# Control.net
KiCad netlist of a schematic drawn in Altium Designer
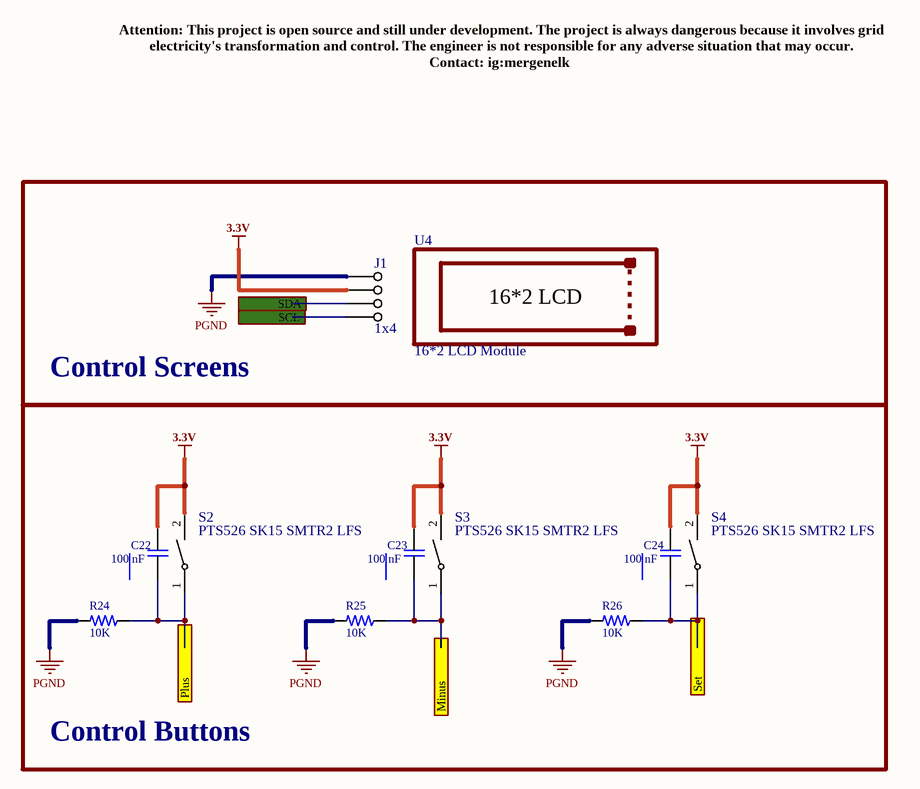
[diagram p0: Control.SchDoc]

(export (version "E")
  (design (tool "Eeschema 10.0.6"))
  (components
    (comp (ref "C22")
      (value "100 nF")
      (footprint "MergenElektronik_Capacitors_Ceramics_SMDs_0603_S_NS")
      (description "Mergen Elektronik - Capacitors - Ceramics - SMDs - 0603 - 100 nF - 16V")
      (fields (field (name "MANUFACTURER") "Samsung") (field (name "TOLERANCE") "±10%"))
      (libsource (lib "MergenElektronik_Capacitors_Ceramics_SMDs") (part "MergenElektronik_Capacitors_Ceramic_SMDs_100nF_16V"))
    )
    (comp (ref "C23")
      (value "100 nF")
      (footprint "MergenElektronik_Capacitors_Ceramics_SMDs_0603_S_NS")
      (description "Mergen Elektronik - Capacitors - Ceramics - SMDs - 0603 - 100 nF - 16V")
      (fields (field (name "MANUFACTURER") "Samsung") (field (name "TOLERANCE") "±10%"))
      (libsource (lib "MergenElektronik_Capacitors_Ceramics_SMDs") (part "MergenElektronik_Capacitors_Ceramic_SMDs_100nF_16V"))
    )
    (comp (ref "C24")
      (value "100 nF")
      (footprint "MergenElektronik_Capacitors_Ceramics_SMDs_0603_S_NS")
      (description "Mergen Elektronik - Capacitors - Ceramics - SMDs - 0603 - 100 nF - 16V")
      (fields (field (name "MANUFACTURER") "Samsung") (field (name "TOLERANCE") "±10%"))
      (libsource (lib "MergenElektronik_Capacitors_Ceramics_SMDs") (part "MergenElektronik_Capacitors_Ceramic_SMDs_100nF_16V"))
    )
    (comp (ref "J1")
      (value "1x4")
      (footprint "MergenElektronik_Connectors_Headers_1x4_Male")
      (description "Mergen Elektronik - Connectors - Headers - 1x4 Male")
      (libsource (lib "MergenElektronik_Connectors_Headers") (part "MergenElektronik_Connectors_Headers_1x4_Male"))
    )
    (comp (ref "R24")
      (value "10K")
      (footprint "MergenElektronik_Resistors_ChipResistors_0603_S_NS")
      (description "Mergen Elektronik - Resistors - Chip Resistors - 0603 - 10K")
      (fields (field (name "MANUFACTURER") "Stackpole") (field (name "POWER") "1/10W"))
      (libsource (lib "MergenElektronik_Resistors_ChipResistors") (part "MergenElektronik_Resistors_ChipResistors_0603_10K"))
    )
    (comp (ref "R25")
      (value "10K")
      (footprint "MergenElektronik_Resistors_ChipResistors_0603_S_NS")
      (description "Mergen Elektronik - Resistors - Chip Resistors - 0603 - 10K")
      (fields (field (name "MANUFACTURER") "Stackpole") (field (name "POWER") "1/10W"))
      (libsource (lib "MergenElektronik_Resistors_ChipResistors") (part "MergenElektronik_Resistors_ChipResistors_0603_10K"))
    )
    (comp (ref "R26")
      (value "10K")
      (footprint "MergenElektronik_Resistors_ChipResistors_0603_S_NS")
      (description "Mergen Elektronik - Resistors - Chip Resistors - 0603 - 10K")
      (fields (field (name "MANUFACTURER") "Stackpole") (field (name "POWER") "1/10W"))
      (libsource (lib "MergenElektronik_Resistors_ChipResistors") (part "MergenElektronik_Resistors_ChipResistors_0603_10K"))
    )
    (comp (ref "S2")
      (value "PTS526 SK15 SMTR2 LFS")
      (footprint "MergenElektronik_Switches_TactileSwitches_PTS526")
      (description "Mergen Elektronik - Switches - Tactile  Switches - PTS526 SK15 SMTR2 LFS")
      (fields (field (name "MANUFACTURER") "C&K"))
      (libsource (lib "MergenElektronik_Switches_TactileSwitches") (part "MergenElektronik_Switches_TactileSwitches_PTS526 SK15 SMTR2 LFS"))
    )
    (comp (ref "S3")
      (value "PTS526 SK15 SMTR2 LFS")
      (footprint "MergenElektronik_Switches_TactileSwitches_PTS526")
      (description "Mergen Elektronik - Switches - Tactile  Switches - PTS526 SK15 SMTR2 LFS")
      (fields (field (name "MANUFACTURER") "C&K"))
      (libsource (lib "MergenElektronik_Switches_TactileSwitches") (part "MergenElektronik_Switches_TactileSwitches_PTS526 SK15 SMTR2 LFS"))
    )
    (comp (ref "S4")
      (value "PTS526 SK15 SMTR2 LFS")
      (footprint "MergenElektronik_Switches_TactileSwitches_PTS526")
      (description "Mergen Elektronik - Switches - Tactile  Switches - PTS526 SK15 SMTR2 LFS")
      (fields (field (name "MANUFACTURER") "C&K"))
      (libsource (lib "MergenElektronik_Switches_TactileSwitches") (part "MergenElektronik_Switches_TactileSwitches_PTS526 SK15 SMTR2 LFS"))
    )
    (comp (ref "U4")
      (value "16*2 LCD Module")
      (footprint "MergenElektronik_Screens_LCDs_16x2Module")
      (description "Mergen Elektronik - Screens - LCDs - 16x2 Module")
      (libsource (lib "MergenElektronik_Screens_LCDs") (part "MergenElektronik_Screens_LCDs_16x2Module"))
    )
  )
  (nets
    (net (code "1") (name "/Minus") (class "Default")
      (node (ref "C23") (pin "2") (pinfunction "2_2") (pintype "passive"))
      (node (ref "R25") (pin "1") (pinfunction "1_1") (pintype "passive"))
      (node (ref "S3") (pin "1") (pinfunction "1_1") (pintype "passive"))
    )
    (net (code "2") (name "/Plus") (class "Default")
      (node (ref "C22") (pin "2") (pinfunction "2_2") (pintype "passive"))
      (node (ref "R24") (pin "1") (pinfunction "1_1") (pintype "passive"))
      (node (ref "S2") (pin "1") (pinfunction "1_1") (pintype "passive"))
    )
    (net (code "3") (name "/SCL") (class "Default")
      (node (ref "J1") (pin "1") (pinfunction "1_1") (pintype "passive"))
    )
    (net (code "4") (name "/SDA") (class "Default")
      (node (ref "J1") (pin "2") (pinfunction "2_2") (pintype "passive"))
    )
    (net (code "5") (name "/Set") (class "Default")
      (node (ref "C24") (pin "2") (pinfunction "2_2") (pintype "passive"))
      (node (ref "R26") (pin "1") (pinfunction "1_1") (pintype "passive"))
      (node (ref "S4") (pin "1") (pinfunction "1_1") (pintype "passive"))
    )
    (net (code "6") (name "3.3V") (class "Default")
      (node (ref "C22") (pin "1") (pinfunction "1_1") (pintype "passive"))
      (node (ref "C23") (pin "1") (pinfunction "1_1") (pintype "passive"))
      (node (ref "C24") (pin "1") (pinfunction "1_1") (pintype "passive"))
      (node (ref "J1") (pin "3") (pinfunction "3_3") (pintype "passive"))
      (node (ref "S2") (pin "2") (pinfunction "2_2") (pintype "passive"))
      (node (ref "S3") (pin "2") (pinfunction "2_2") (pintype "passive"))
      (node (ref "S4") (pin "2") (pinfunction "2_2") (pintype "passive"))
    )
    (net (code "7") (name "PGND") (class "Default")
      (node (ref "J1") (pin "4") (pinfunction "4_4") (pintype "passive"))
      (node (ref "R24") (pin "2") (pinfunction "2_2") (pintype "passive"))
      (node (ref "R25") (pin "2") (pinfunction "2_2") (pintype "passive"))
      (node (ref "R26") (pin "2") (pinfunction "2_2") (pintype "passive"))
    )
  )
)
